# 11_MEM_HYPERRAM_FLASH.net
KiCad netlist of a schematic drawn in Altium Designer
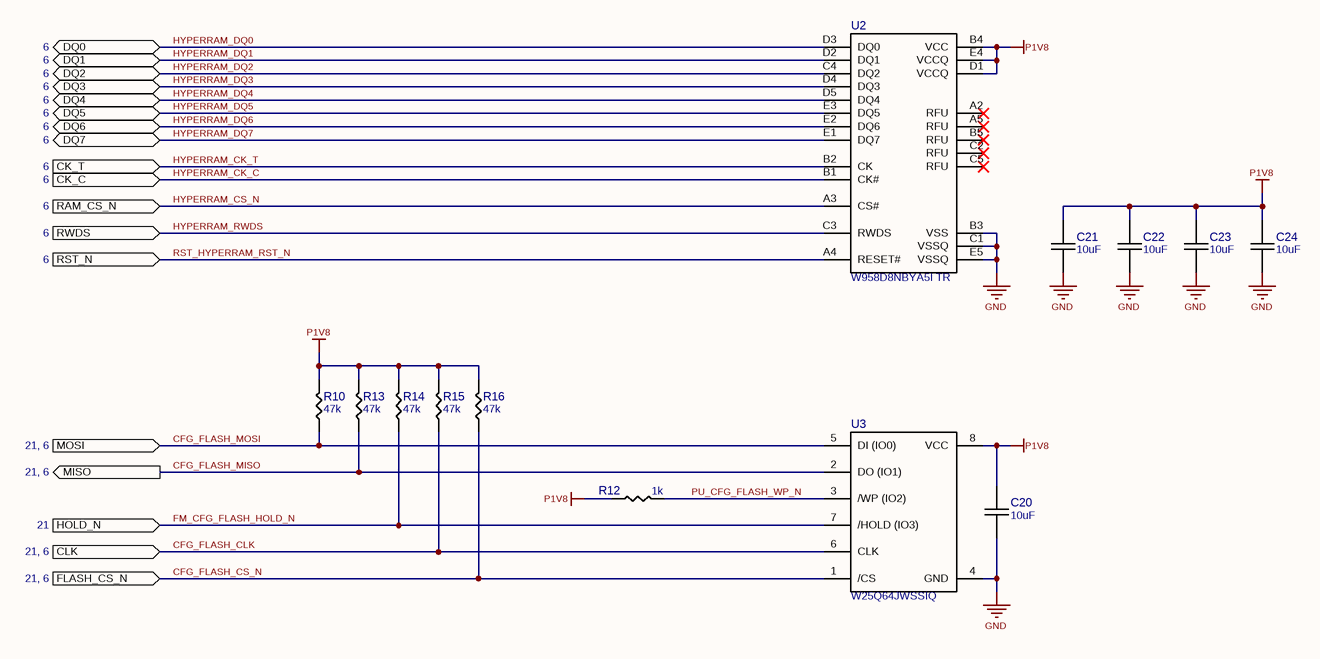
[diagram p0: 11_MEM_HYPERRAM_FLASH.SchDoc]

(export (version "E")
  (design (tool "Eeschema 10.0.6"))
  (components
    (comp (ref "C20")
      (value "10uF")
      (footprint "CAPC1005X06N")
      (description "CAP CER 10UF 6.3V X5R 0402")
      (fields (field (name "PART NUMBER") "GRM155R60J106ME47D") (field (name "VOLTAGE") "6.3V"))
      (libsource (lib "Database") (part "Capacitor"))
    )
    (comp (ref "C21")
      (value "10uF")
      (footprint "CAPC1005X06N")
      (description "CAP CER 10UF 6.3V X5R 0402")
      (fields (field (name "PART NUMBER") "GRM155R60J106ME47D") (field (name "VOLTAGE") "6.3V"))
      (libsource (lib "Database") (part "Capacitor"))
    )
    (comp (ref "C22")
      (value "10uF")
      (footprint "CAPC1005X06N")
      (description "CAP CER 10UF 6.3V X5R 0402")
      (fields (field (name "PART NUMBER") "GRM155R60J106ME47D") (field (name "VOLTAGE") "6.3V"))
      (libsource (lib "Database") (part "Capacitor"))
    )
    (comp (ref "C23")
      (value "10uF")
      (footprint "CAPC1005X06N")
      (description "CAP CER 10UF 6.3V X5R 0402")
      (fields (field (name "PART NUMBER") "GRM155R60J106ME47D") (field (name "VOLTAGE") "6.3V"))
      (libsource (lib "Database") (part "Capacitor"))
    )
    (comp (ref "C24")
      (value "10uF")
      (footprint "CAPC1005X06N")
      (description "CAP CER 10UF 6.3V X5R 0402")
      (fields (field (name "PART NUMBER") "GRM155R60J106ME47D") (field (name "VOLTAGE") "6.3V"))
      (libsource (lib "Database") (part "Capacitor"))
    )
    (comp (ref "R10")
      (value "47k")
      (footprint "RESC1005X03N")
      (description "RES SMD 47K OHM 1% 1/16W 0402")
      (fields (field (name "PART NUMBER") "RC0402FR-0747KL"))
      (libsource (lib "Database") (part "Resistor_ENG"))
    )
    (comp (ref "R12")
      (value "1k")
      (footprint "RESC1005X03N")
      (description "RES SMD 1K OHM 1% 1/16W 0402")
      (fields (field (name "PART NUMBER") "RC0402FR-071KL"))
      (libsource (lib "Database") (part "Resistor_ENG"))
    )
    (comp (ref "R13")
      (value "47k")
      (footprint "RESC1005X03N")
      (description "RES SMD 47K OHM 1% 1/16W 0402")
      (fields (field (name "PART NUMBER") "RC0402FR-0747KL"))
      (libsource (lib "Database") (part "Resistor_ENG"))
    )
    (comp (ref "R14")
      (value "47k")
      (footprint "RESC1005X03N")
      (description "RES SMD 47K OHM 1% 1/16W 0402")
      (fields (field (name "PART NUMBER") "RC0402FR-0747KL"))
      (libsource (lib "Database") (part "Resistor_ENG"))
    )
    (comp (ref "R15")
      (value "47k")
      (footprint "RESC1005X03N")
      (description "RES SMD 47K OHM 1% 1/16W 0402")
      (fields (field (name "PART NUMBER") "RC0402FR-0747KL"))
      (libsource (lib "Database") (part "Resistor_ENG"))
    )
    (comp (ref "R16")
      (value "47k")
      (footprint "RESC1005X03N")
      (description "RES SMD 47K OHM 1% 1/16W 0402")
      (fields (field (name "PART NUMBER") "RC0402FR-0747KL"))
      (libsource (lib "Database") (part "Resistor_ENG"))
    )
    (comp (ref "U2")
      (value "W958D8NBYA5I TR")
      (footprint "BGA24C100P5X5_600X800X120")
      (description "256MB HYPERRAM X8, 200MHZ, IND T")
      (libsource (lib "Database") (part "W958D8NBYAxx"))
    )
    (comp (ref "U3")
      (value "W25Q64JWSSIQ")
      (footprint "SOIC127P590X175-8N")
      (description "IC FLASH 64MBIT SPI/QUAD 8SOIC")
      (libsource (lib "Database") (part "W25Q64JWSSIQ"))
    )
  )
  (nets
    (net (code "1") (name "/CFG_FLASH_CLK") (class "Default")
      (node (ref "R15") (pin "1") (pinfunction "1_1") (pintype "passive"))
      (node (ref "U3") (pin "6") (pinfunction "CLK_6") (pintype "passive"))
    )
    (net (code "2") (name "/CFG_FLASH_CS_N") (class "Default")
      (node (ref "R16") (pin "1") (pinfunction "1_1") (pintype "passive"))
      (node (ref "U3") (pin "1") (pinfunction "/CS_1") (pintype "passive"))
    )
    (net (code "3") (name "/CFG_FLASH_MISO") (class "Default")
      (node (ref "R13") (pin "1") (pinfunction "1_1") (pintype "passive"))
      (node (ref "U3") (pin "2") (pinfunction "DO_(IO1)_2") (pintype "passive"))
    )
    (net (code "4") (name "/CFG_FLASH_MOSI") (class "Default")
      (node (ref "R10") (pin "1") (pinfunction "1_1") (pintype "passive"))
      (node (ref "U3") (pin "5") (pinfunction "DI_(IO0)_5") (pintype "passive"))
    )
    (net (code "5") (name "/FM_CFG_FLASH_HOLD_N") (class "Default")
      (node (ref "R14") (pin "1") (pinfunction "1_1") (pintype "passive"))
      (node (ref "U3") (pin "7") (pinfunction "/HOLD_(IO3)_7") (pintype "passive"))
    )
    (net (code "6") (name "/HYPERRAM_CK_C") (class "Default")
      (node (ref "U2") (pin "B1") (pinfunction "CK#_B1") (pintype "passive"))
    )
    (net (code "7") (name "/HYPERRAM_CK_T") (class "Default")
      (node (ref "U2") (pin "B2") (pinfunction "CK_B2") (pintype "passive"))
    )
    (net (code "8") (name "/HYPERRAM_CS_N") (class "Default")
      (node (ref "U2") (pin "A3") (pinfunction "CS#_A3") (pintype "passive"))
    )
    (net (code "9") (name "/HYPERRAM_DQ0") (class "Default")
      (node (ref "U2") (pin "D3") (pinfunction "DQ0_D3") (pintype "passive"))
    )
    (net (code "10") (name "/HYPERRAM_DQ1") (class "Default")
      (node (ref "U2") (pin "D2") (pinfunction "DQ1_D2") (pintype "passive"))
    )
    (net (code "11") (name "/HYPERRAM_DQ2") (class "Default")
      (node (ref "U2") (pin "C4") (pinfunction "DQ2_C4") (pintype "passive"))
    )
    (net (code "12") (name "/HYPERRAM_DQ3") (class "Default")
      (node (ref "U2") (pin "D4") (pinfunction "DQ3_D4") (pintype "passive"))
    )
    (net (code "13") (name "/HYPERRAM_DQ4") (class "Default")
      (node (ref "U2") (pin "D5") (pinfunction "DQ4_D5") (pintype "passive"))
    )
    (net (code "14") (name "/HYPERRAM_DQ5") (class "Default")
      (node (ref "U2") (pin "E3") (pinfunction "DQ5_E3") (pintype "passive"))
    )
    (net (code "15") (name "/HYPERRAM_DQ6") (class "Default")
      (node (ref "U2") (pin "E2") (pinfunction "DQ6_E2") (pintype "passive"))
    )
    (net (code "16") (name "/HYPERRAM_DQ7") (class "Default")
      (node (ref "U2") (pin "E1") (pinfunction "DQ7_E1") (pintype "passive"))
    )
    (net (code "17") (name "/HYPERRAM_RWDS") (class "Default")
      (node (ref "U2") (pin "C3") (pinfunction "RWDS_C3") (pintype "passive"))
    )
    (net (code "18") (name "/PU_CFG_FLASH_WP_N") (class "Default")
      (node (ref "R12") (pin "2") (pinfunction "2_2") (pintype "passive"))
      (node (ref "U3") (pin "3") (pinfunction "/WP_(IO2)_3") (pintype "passive"))
    )
    (net (code "19") (name "/RST_HYPERRAM_RST_N") (class "Default")
      (node (ref "U2") (pin "A4") (pinfunction "RESET#_A4") (pintype "passive"))
    )
    (net (code "20") (name "GND") (class "Default")
      (node (ref "C20") (pin "1") (pinfunction "1_1") (pintype "passive"))
      (node (ref "C21") (pin "1") (pinfunction "1_1") (pintype "passive"))
      (node (ref "C22") (pin "1") (pinfunction "1_1") (pintype "passive"))
      (node (ref "C23") (pin "1") (pinfunction "1_1") (pintype "passive"))
      (node (ref "C24") (pin "1") (pinfunction "1_1") (pintype "passive"))
      (node (ref "U2") (pin "B3") (pinfunction "VSS_B3") (pintype "passive"))
      (node (ref "U2") (pin "C1") (pinfunction "VSSQ_C1") (pintype "passive"))
      (node (ref "U2") (pin "E5") (pinfunction "VSSQ_E5") (pintype "passive"))
      (node (ref "U3") (pin "4") (pinfunction "GND_4") (pintype "passive"))
    )
    (net (code "21") (name "P1V8") (class "Default")
      (node (ref "C20") (pin "2") (pinfunction "2_2") (pintype "passive"))
      (node (ref "C21") (pin "2") (pinfunction "2_2") (pintype "passive"))
      (node (ref "C22") (pin "2") (pinfunction "2_2") (pintype "passive"))
      (node (ref "C23") (pin "2") (pinfunction "2_2") (pintype "passive"))
      (node (ref "C24") (pin "2") (pinfunction "2_2") (pintype "passive"))
      (node (ref "R10") (pin "2") (pinfunction "2_2") (pintype "passive"))
      (node (ref "R12") (pin "1") (pinfunction "1_1") (pintype "passive"))
      (node (ref "R13") (pin "2") (pinfunction "2_2") (pintype "passive"))
      (node (ref "R14") (pin "2") (pinfunction "2_2") (pintype "passive"))
      (node (ref "R15") (pin "2") (pinfunction "2_2") (pintype "passive"))
      (node (ref "R16") (pin "2") (pinfunction "2_2") (pintype "passive"))
      (node (ref "U2") (pin "B4") (pinfunction "VCC_B4") (pintype "passive"))
      (node (ref "U2") (pin "D1") (pinfunction "VCCQ_D1") (pintype "passive"))
      (node (ref "U2") (pin "E4") (pinfunction "VCCQ_E4") (pintype "passive"))
      (node (ref "U3") (pin "8") (pinfunction "VCC_8") (pintype "passive"))
    )
    (net (code "22") (name "unconnected-(U2-RFU-PadA2)") (class "Default")
      (node (ref "U2") (pin "A2") (pinfunction "RFU_A2") (pintype "passive+no_connect"))
    )
    (net (code "23") (name "unconnected-(U2-RFU-PadA5)") (class "Default")
      (node (ref "U2") (pin "A5") (pinfunction "RFU_A5") (pintype "passive+no_connect"))
    )
    (net (code "24") (name "unconnected-(U2-RFU-PadB5)") (class "Default")
      (node (ref "U2") (pin "B5") (pinfunction "RFU_B5") (pintype "passive+no_connect"))
    )
    (net (code "25") (name "unconnected-(U2-RFU-PadC2)") (class "Default")
      (node (ref "U2") (pin "C2") (pinfunction "RFU_C2") (pintype "passive+no_connect"))
    )
    (net (code "26") (name "unconnected-(U2-RFU-PadC5)") (class "Default")
      (node (ref "U2") (pin "C5") (pinfunction "RFU_C5") (pintype "passive+no_connect"))
    )
  )
)
